# AUDIO.net
KiCad netlist of a schematic drawn in Altium Designer
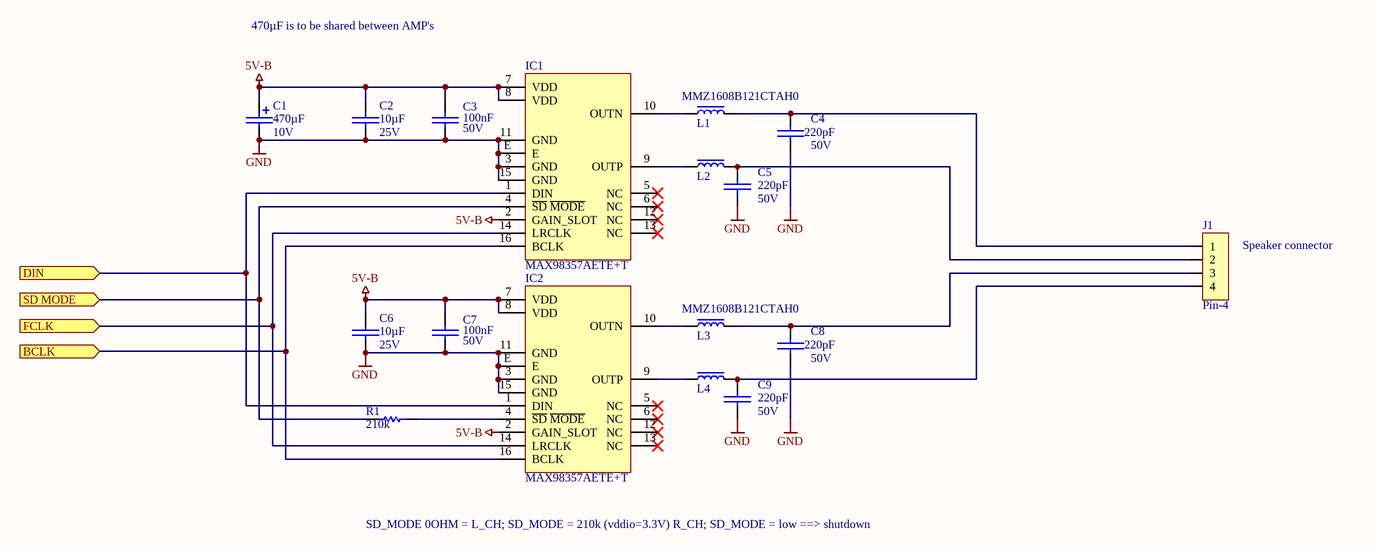
[diagram p0: AUDIO.SchDoc]

(export (version "E")
  (design (tool "Eeschema 10.0.6"))
  (components
    (comp (ref "C1")
      (value "470µF")
      (footprint "CD6.3H12TH")
      (description "CAP ALUM 470UF 20% 10V TH")
      (fields
        (field (name "MANUFACTURER") "AISHI(Aihua Group)")
        (field (name "TOLERANCE") "20%")
        (field (name "VOLTAGE") "10V")
      )
      (libsource (lib "bond-altium-excell") (part "cap-pol"))
    )
    (comp (ref "C2")
      (value "10µF")
      (footprint "C0603")
      (description "CAP CER 10UF 25V X5R 10% SMD")
      (fields
        (field (name "MANUFACTURER") "Murata Electronics")
        (field (name "TOLERANCE") "10%")
        (field (name "VOLTAGE") "25V")
      )
      (libsource (lib "bond-altium-excell") (part "cap_non_pol"))
    )
    (comp (ref "C3")
      (value "100nF")
      (footprint "C0402")
      (description "CAP CER 0.1UF 50V X5R 0402")
      (fields
        (field (name "MANUFACTURER") "Murata Electronics")
        (field (name "TOLERANCE") "5%")
        (field (name "VOLTAGE") "50V")
      )
      (libsource (lib "bond-altium-excell") (part "cap_non_pol"))
    )
    (comp (ref "C4")
      (value "220pF")
      (footprint "TH5.08")
      (description "CAP CER TH 220pF NP0 50V")
      (fields
        (field (name "MANUFACTURER") "WMEC")
        (field (name "TOLERANCE") "5%")
        (field (name "VOLTAGE") "50V")
      )
      (libsource (lib "bond-altium-excell") (part "cap_non_pol"))
    )
    (comp (ref "C5")
      (value "220pF")
      (footprint "TH5.08")
      (description "CAP CER TH 220pF NP0 50V")
      (fields
        (field (name "MANUFACTURER") "WMEC")
        (field (name "TOLERANCE") "5%")
        (field (name "VOLTAGE") "50V")
      )
      (libsource (lib "bond-altium-excell") (part "cap_non_pol"))
    )
    (comp (ref "C6")
      (value "10µF")
      (footprint "C0603")
      (description "CAP CER 10UF 25V X5R 10% SMD")
      (fields
        (field (name "MANUFACTURER") "Murata Electronics")
        (field (name "TOLERANCE") "10%")
        (field (name "VOLTAGE") "25V")
      )
      (libsource (lib "bond-altium-excell") (part "cap_non_pol"))
    )
    (comp (ref "C7")
      (value "100nF")
      (footprint "C0402")
      (description "CAP CER 0.1UF 50V X5R 0402")
      (fields
        (field (name "MANUFACTURER") "Murata Electronics")
        (field (name "TOLERANCE") "5%")
        (field (name "VOLTAGE") "50V")
      )
      (libsource (lib "bond-altium-excell") (part "cap_non_pol"))
    )
    (comp (ref "C8")
      (value "220pF")
      (footprint "TH5.08")
      (description "CAP CER TH 220pF NP0 50V")
      (fields
        (field (name "MANUFACTURER") "WMEC")
        (field (name "TOLERANCE") "5%")
        (field (name "VOLTAGE") "50V")
      )
      (libsource (lib "bond-altium-excell") (part "cap_non_pol"))
    )
    (comp (ref "C9")
      (value "220pF")
      (footprint "TH5.08")
      (description "CAP CER TH 220pF NP0 50V")
      (fields
        (field (name "MANUFACTURER") "WMEC")
        (field (name "TOLERANCE") "5%")
        (field (name "VOLTAGE") "50V")
      )
      (libsource (lib "bond-altium-excell") (part "cap_non_pol"))
    )
    (comp (ref "IC1")
      (value "MAX98357AETE+T")
      (footprint "TQFN-16")
      (description "IC AMP CLASS D MONO 3.2W 16TQFN")
      (fields (field (name "MANUFACTURER") "Maxim Integrated"))
      (libsource (lib "bond-altium-excell") (part "MAX98357AETE+T"))
    )
    (comp (ref "IC2")
      (value "MAX98357AETE+T")
      (footprint "TQFN-16")
      (description "IC AMP CLASS D MONO 3.2W 16TQFN")
      (fields (field (name "MANUFACTURER") "Maxim Integrated"))
      (libsource (lib "bond-altium-excell") (part "MAX98357AETE+T"))
    )
    (comp (ref "J1")
      (value "Pin-4")
      (footprint "110990030")
      (description "GROVE 2MM 4PIN VERT CONN 10PCS")
      (fields (field (name "MANUFACTURER") "Seeed Technology Co., Ltd"))
      (libsource (lib "bond-altium-excell") (part "Pin-4"))
    )
    (comp (ref "L1")
      (value "ferrite_bead")
      (footprint "FB0603")
      (description "FERRITE BEAD 120 OHM 0603 1LN")
      (fields
        (field (name "MANUFACTURER_REF") "MMZ1608B121CTAH0")
        (field (name "MANUFACTURER") "TDK Corporation")
      )
      (libsource (lib "bond-altium-excell") (part "ferrite_bead"))
    )
    (comp (ref "L2")
      (value "ferrite_bead")
      (footprint "FB0603")
      (description "FERRITE BEAD 120 OHM 0603 1LN")
      (fields (field (name "MANUFACTURER") "TDK Corporation"))
      (libsource (lib "bond-altium-excell") (part "ferrite_bead"))
    )
    (comp (ref "L3")
      (value "ferrite_bead")
      (footprint "FB0603")
      (description "FERRITE BEAD 120 OHM 0603 1LN")
      (fields
        (field (name "MANUFACTURER_REF") "MMZ1608B121CTAH0")
        (field (name "MANUFACTURER") "TDK Corporation")
      )
      (libsource (lib "bond-altium-excell") (part "ferrite_bead"))
    )
    (comp (ref "L4")
      (value "ferrite_bead")
      (footprint "FB0603")
      (description "FERRITE BEAD 120 OHM 0603 1LN")
      (fields (field (name "MANUFACTURER") "TDK Corporation"))
      (libsource (lib "bond-altium-excell") (part "ferrite_bead"))
    )
    (comp (ref "R1")
      (value "210k")
      (footprint "R0402")
      (description "RES 210K OHM 1% 1/16W 0402")
      (fields (field (name "MANUFACTURER") "YAGEO") (field (name "TOLERANCE") "1%"))
      (libsource (lib "bond-altium-excell") (part "resistor"))
    )
  )
  (nets
    (net (code "1") (name "/BCLK") (class "Default")
      (node (ref "IC1") (pin "16") (pinfunction "BCLK_16") (pintype "passive"))
      (node (ref "IC2") (pin "16") (pinfunction "BCLK_16") (pintype "passive"))
    )
    (net (code "2") (name "/DIN") (class "Default")
      (node (ref "IC1") (pin "1") (pinfunction "DIN_1") (pintype "passive"))
      (node (ref "IC2") (pin "1") (pinfunction "DIN_1") (pintype "passive"))
    )
    (net (code "3") (name "/FCLK") (class "Default")
      (node (ref "IC1") (pin "14") (pinfunction "LRCLK_14") (pintype "passive"))
      (node (ref "IC2") (pin "14") (pinfunction "LRCLK_14") (pintype "passive"))
    )
    (net (code "4") (name "/SD MODE") (class "Default")
      (node (ref "IC1") (pin "4") (pinfunction "~{SD}_~{MODE}_4") (pintype "passive"))
      (node (ref "R1") (pin "2") (pinfunction "2_2") (pintype "passive"))
    )
    (net (code "5") (name "5V-B") (class "Default")
      (node (ref "C1") (pin "+") (pinfunction "+_+") (pintype "passive"))
      (node (ref "C2") (pin "1") (pinfunction "1_1") (pintype "passive"))
      (node (ref "C3") (pin "2") (pinfunction "2_2") (pintype "passive"))
      (node (ref "C6") (pin "1") (pinfunction "1_1") (pintype "passive"))
      (node (ref "C7") (pin "2") (pinfunction "2_2") (pintype "passive"))
      (node (ref "IC1") (pin "2") (pinfunction "GAIN_SLOT_2") (pintype "passive"))
      (node (ref "IC1") (pin "7") (pinfunction "VDD_7") (pintype "passive"))
      (node (ref "IC1") (pin "8") (pinfunction "VDD_8") (pintype "passive"))
      (node (ref "IC2") (pin "2") (pinfunction "GAIN_SLOT_2") (pintype "passive"))
      (node (ref "IC2") (pin "7") (pinfunction "VDD_7") (pintype "passive"))
      (node (ref "IC2") (pin "8") (pinfunction "VDD_8") (pintype "passive"))
    )
    (net (code "6") (name "GND") (class "Default")
      (node (ref "C1") (pin "-") (pinfunction "-_-") (pintype "passive"))
      (node (ref "C2") (pin "2") (pinfunction "2_2") (pintype "passive"))
      (node (ref "C3") (pin "1") (pinfunction "1_1") (pintype "passive"))
      (node (ref "C4") (pin "2") (pinfunction "2_2") (pintype "passive"))
      (node (ref "C5") (pin "2") (pinfunction "2_2") (pintype "passive"))
      (node (ref "C6") (pin "2") (pinfunction "2_2") (pintype "passive"))
      (node (ref "C7") (pin "1") (pinfunction "1_1") (pintype "passive"))
      (node (ref "C8") (pin "2") (pinfunction "2_2") (pintype "passive"))
      (node (ref "C9") (pin "2") (pinfunction "2_2") (pintype "passive"))
      (node (ref "IC1") (pin "11") (pinfunction "GND_11") (pintype "passive"))
      (node (ref "IC1") (pin "15") (pinfunction "GND_15") (pintype "passive"))
      (node (ref "IC1") (pin "3") (pinfunction "GND_3") (pintype "passive"))
      (node (ref "IC1") (pin "E") (pinfunction "E_E") (pintype "passive"))
      (node (ref "IC2") (pin "11") (pinfunction "GND_11") (pintype "passive"))
      (node (ref "IC2") (pin "15") (pinfunction "GND_15") (pintype "passive"))
      (node (ref "IC2") (pin "3") (pinfunction "GND_3") (pintype "passive"))
      (node (ref "IC2") (pin "E") (pinfunction "E_E") (pintype "passive"))
    )
    (net (code "7") (name "Net-(C4-Pad1)") (class "Default")
      (node (ref "C4") (pin "1") (pinfunction "1_1") (pintype "passive"))
      (node (ref "J1") (pin "1") (pinfunction "1_1") (pintype "passive"))
      (node (ref "L1") (pin "2") (pinfunction "2_2") (pintype "passive"))
    )
    (net (code "8") (name "Net-(C5-Pad1)") (class "Default")
      (node (ref "C5") (pin "1") (pinfunction "1_1") (pintype "passive"))
      (node (ref "J1") (pin "2") (pinfunction "2_2") (pintype "passive"))
      (node (ref "L2") (pin "2") (pinfunction "2_2") (pintype "passive"))
    )
    (net (code "9") (name "Net-(C8-Pad1)") (class "Default")
      (node (ref "C8") (pin "1") (pinfunction "1_1") (pintype "passive"))
      (node (ref "J1") (pin "3") (pinfunction "3_3") (pintype "passive"))
      (node (ref "L3") (pin "2") (pinfunction "2_2") (pintype "passive"))
    )
    (net (code "10") (name "Net-(C9-Pad1)") (class "Default")
      (node (ref "C9") (pin "1") (pinfunction "1_1") (pintype "passive"))
      (node (ref "J1") (pin "4") (pinfunction "4_4") (pintype "passive"))
      (node (ref "L4") (pin "2") (pinfunction "2_2") (pintype "passive"))
    )
    (net (code "11") (name "Net-(IC1-OUTN)") (class "Default")
      (node (ref "IC1") (pin "10") (pinfunction "OUTN_10") (pintype "passive"))
      (node (ref "L1") (pin "1") (pinfunction "1_1") (pintype "passive"))
    )
    (net (code "12") (name "Net-(IC1-OUTP)") (class "Default")
      (node (ref "IC1") (pin "9") (pinfunction "OUTP_9") (pintype "passive"))
      (node (ref "L2") (pin "1") (pinfunction "1_1") (pintype "passive"))
    )
    (net (code "13") (name "Net-(IC2-OUTN)") (class "Default")
      (node (ref "IC2") (pin "10") (pinfunction "OUTN_10") (pintype "passive"))
      (node (ref "L3") (pin "1") (pinfunction "1_1") (pintype "passive"))
    )
    (net (code "14") (name "Net-(IC2-OUTP)") (class "Default")
      (node (ref "IC2") (pin "9") (pinfunction "OUTP_9") (pintype "passive"))
      (node (ref "L4") (pin "1") (pinfunction "1_1") (pintype "passive"))
    )
    (net (code "15") (name "Net-(IC2-~{SD}_~{MODE})") (class "Default")
      (node (ref "IC2") (pin "4") (pinfunction "~{SD}_~{MODE}_4") (pintype "passive"))
      (node (ref "R1") (pin "1") (pinfunction "1_1") (pintype "passive"))
    )
    (net (code "16") (name "unconnected-(IC1-NC-Pad5)") (class "Default")
      (node (ref "IC1") (pin "5") (pinfunction "NC_5") (pintype "passive+no_connect"))
    )
    (net (code "17") (name "unconnected-(IC1-NC-Pad6)") (class "Default")
      (node (ref "IC1") (pin "6") (pinfunction "NC_6") (pintype "passive+no_connect"))
    )
    (net (code "18") (name "unconnected-(IC1-NC-Pad12)") (class "Default")
      (node (ref "IC1") (pin "12") (pinfunction "NC_12") (pintype "passive+no_connect"))
    )
    (net (code "19") (name "unconnected-(IC1-NC-Pad13)") (class "Default")
      (node (ref "IC1") (pin "13") (pinfunction "NC_13") (pintype "passive+no_connect"))
    )
    (net (code "20") (name "unconnected-(IC2-NC-Pad5)") (class "Default")
      (node (ref "IC2") (pin "5") (pinfunction "NC_5") (pintype "passive+no_connect"))
    )
    (net (code "21") (name "unconnected-(IC2-NC-Pad6)") (class "Default")
      (node (ref "IC2") (pin "6") (pinfunction "NC_6") (pintype "passive+no_connect"))
    )
    (net (code "22") (name "unconnected-(IC2-NC-Pad12)") (class "Default")
      (node (ref "IC2") (pin "12") (pinfunction "NC_12") (pintype "passive+no_connect"))
    )
    (net (code "23") (name "unconnected-(IC2-NC-Pad13)") (class "Default")
      (node (ref "IC2") (pin "13") (pinfunction "NC_13") (pintype "passive+no_connect"))
    )
  )
)
